# Sheet1.net
KiCad netlist of a schematic drawn in Altium Designer
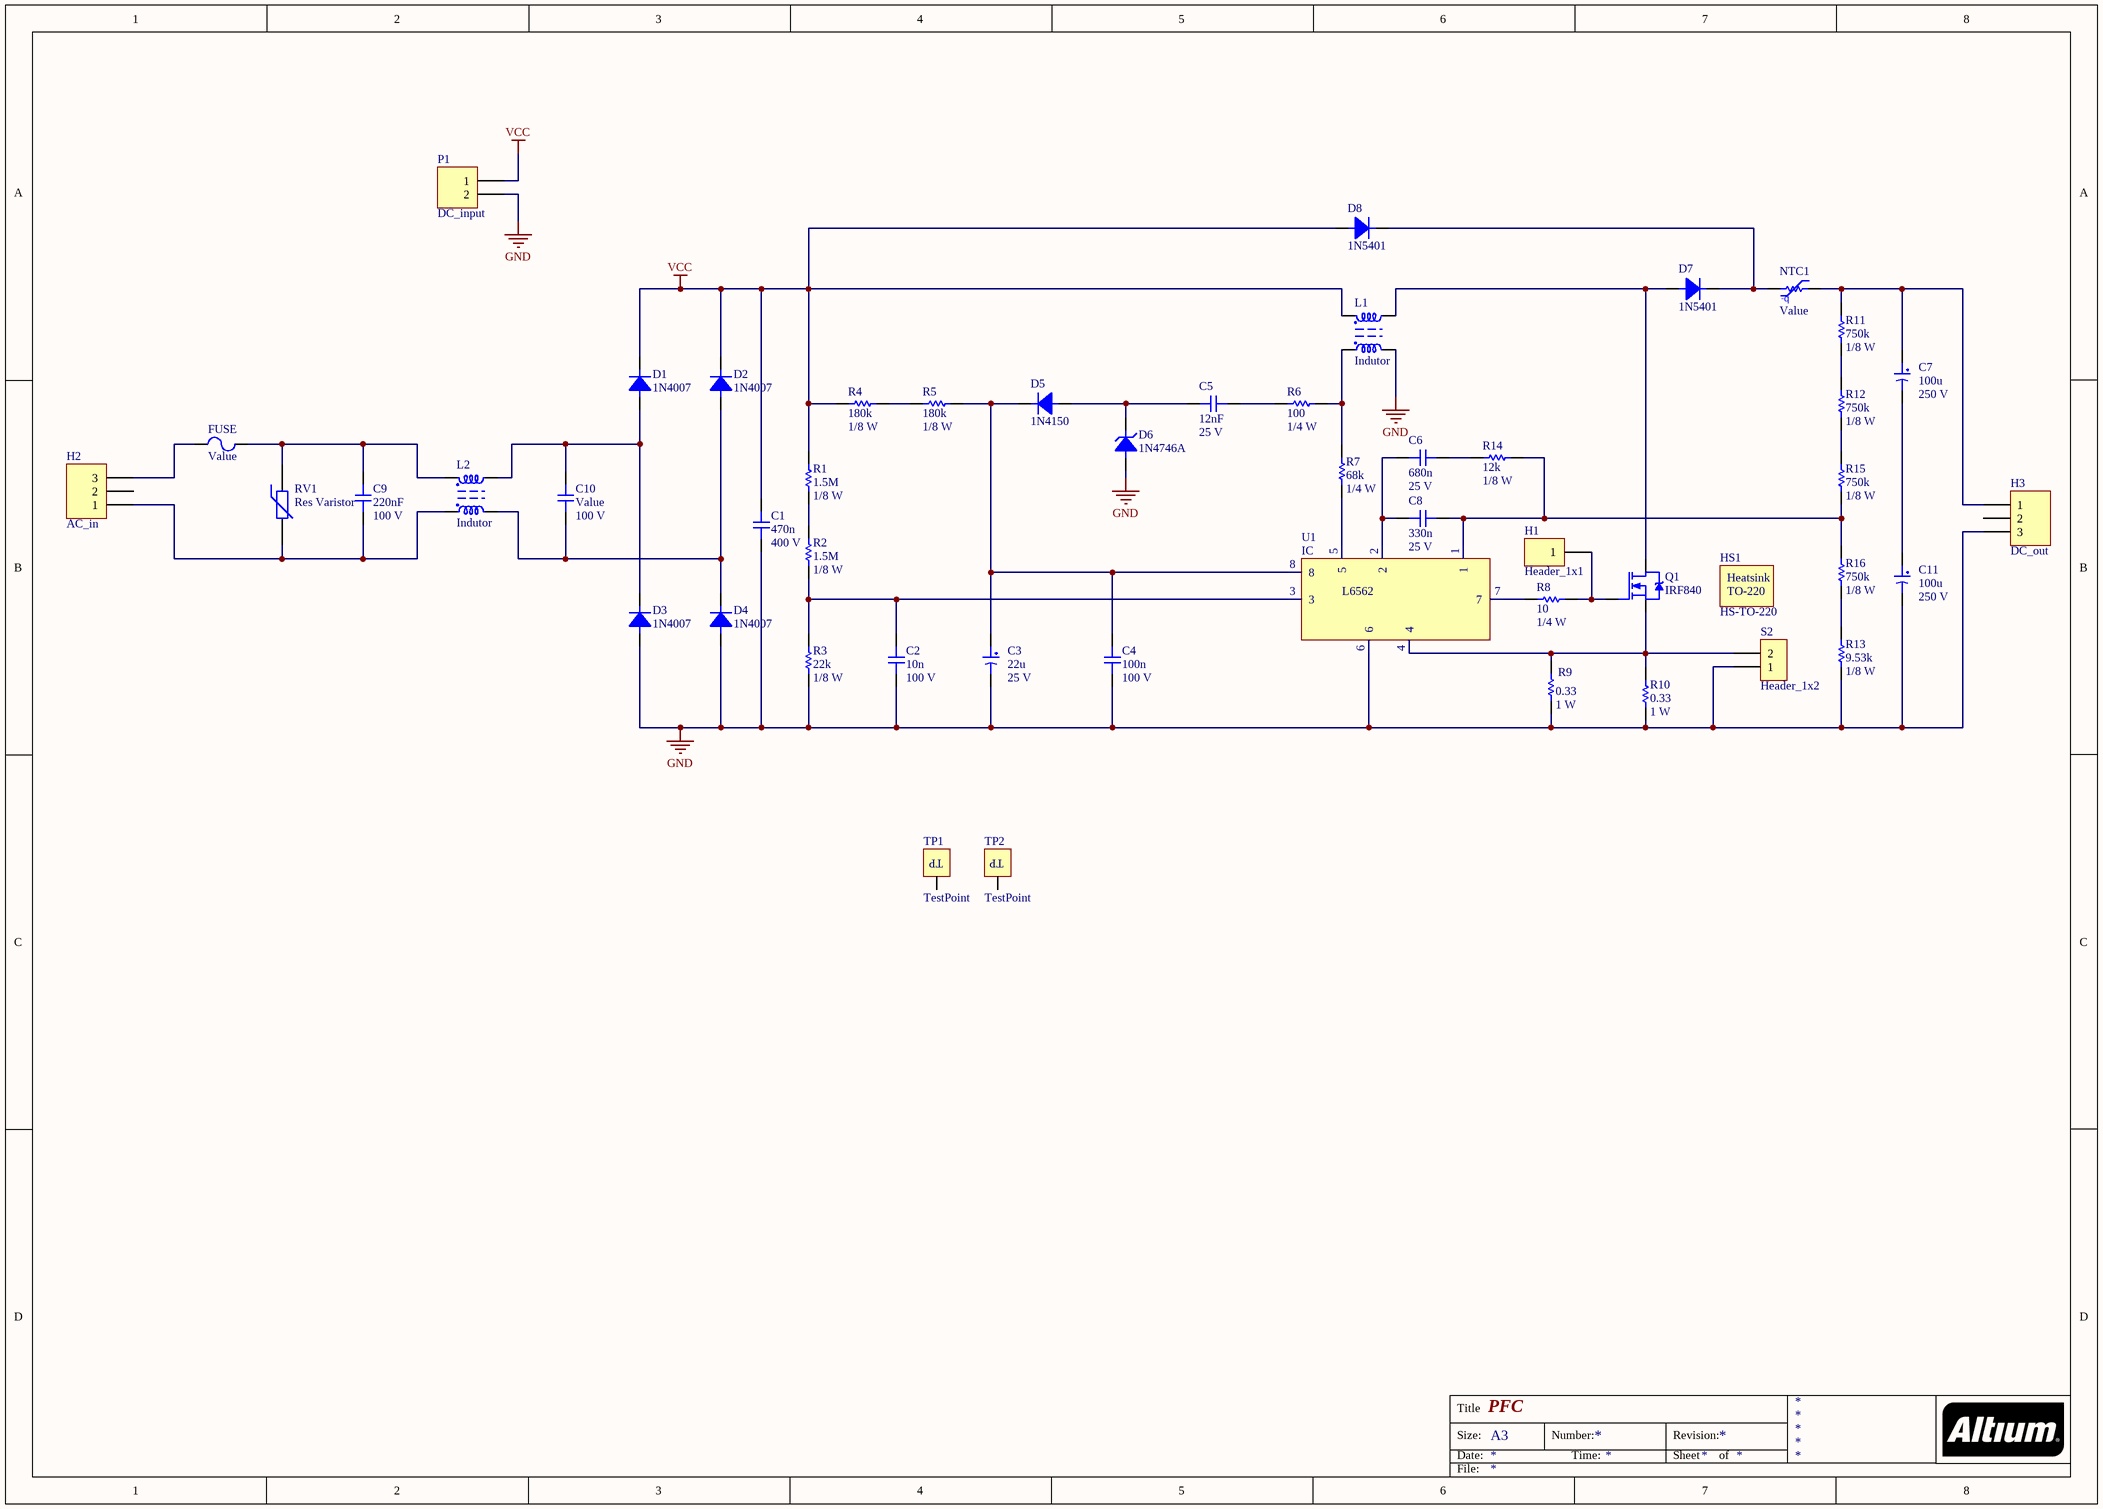
[diagram p0: Sheet1.SchDoc]

(export (version "E")
  (design (tool "Eeschema 10.0.6"))
  (components
    (comp (ref "C1")
      (value "470n")
      (footprint "AXIAL-1.0")
      (description "Capacitor")
      (fields (field (name "VOLTAGE") "400 V") (field (name "PUBLISHER") "Altium Limited"))
      (libsource (lib "GPDSE") (part "Capacitor"))
    )
    (comp (ref "C2")
      (value "10n")
      (footprint "0805C")
      (description "Capacitor")
      (fields (field (name "VOLTAGE") "100 V") (field (name "PUBLISHER") "Altium Limited"))
      (libsource (lib "GPDSE") (part "Capacitor"))
    )
    (comp (ref "C3")
      (value "22u")
      (footprint "CP-5.0mm-11.0mm-2.0mm")
      (description "Electrolytic Capacitor")
      (fields (field (name "VOLTAGE") "25 V"))
      (libsource (lib "GPDSE") (part "Capacitor-Electrolytic"))
    )
    (comp (ref "C4")
      (value "100n")
      (footprint "0805C")
      (description "Capacitor")
      (fields (field (name "VOLTAGE") "100 V") (field (name "PUBLISHER") "Altium Limited"))
      (libsource (lib "GPDSE") (part "Capacitor"))
    )
    (comp (ref "C5")
      (value "12nF")
      (footprint "C100-200-100")
      (description "Capacitor")
      (fields (field (name "VOLTAGE") "25 V") (field (name "PUBLISHER") "Altium Limited"))
      (libsource (lib "GPDSE") (part "Capacitor"))
    )
    (comp (ref "C6")
      (value "680n")
      (footprint "C200-350-150")
      (description "Capacitor")
      (fields (field (name "VOLTAGE") "25 V") (field (name "PUBLISHER") "Altium Limited"))
      (libsource (lib "GPDSE") (part "Capacitor"))
    )
    (comp (ref "C7")
      (value "100u")
      (footprint "CP-16.0mm-25.0mm-7.5mm")
      (description "Electrolytic Capacitor")
      (fields (field (name "VOLTAGE") "250 V"))
      (libsource (lib "GPDSE") (part "Capacitor-Electrolytic"))
    )
    (comp (ref "C8")
      (value "330n")
      (footprint "C200-350-150")
      (description "Capacitor")
      (fields (field (name "VOLTAGE") "25 V") (field (name "PUBLISHER") "Altium Limited"))
      (libsource (lib "GPDSE") (part "Capacitor"))
    )
    (comp (ref "C9")
      (value "220nF")
      (footprint "C590-695-330")
      (description "Capacitor")
      (fields (field (name "VOLTAGE") "100 V") (field (name "PUBLISHER") "Altium Limited"))
      (libsource (lib "GPDSE") (part "Capacitor"))
    )
    (comp (ref "C10")
      (value "Value")
      (footprint "C590-695-330")
      (description "Capacitor")
      (fields (field (name "VOLTAGE") "100 V") (field (name "PUBLISHER") "Altium Limited"))
      (libsource (lib "GPDSE") (part "Capacitor"))
    )
    (comp (ref "C11")
      (value "100u")
      (footprint "CP-16.0mm-25.0mm-7.5mm")
      (description "Electrolytic Capacitor")
      (fields (field (name "VOLTAGE") "250 V"))
      (libsource (lib "GPDSE") (part "Capacitor-Electrolytic"))
    )
    (comp (ref "D1")
      (value "1N4007")
      (footprint "DO-41-Plastic")
      (description "General Purpose Rectifier")
      (libsource (lib "GPDSE") (part "1N4007"))
    )
    (comp (ref "D2")
      (value "1N4007")
      (footprint "DO-41-Plastic")
      (description "General Purpose Rectifier")
      (libsource (lib "GPDSE") (part "1N4007"))
    )
    (comp (ref "D3")
      (value "1N4007")
      (footprint "DO-41-Plastic")
      (description "General Purpose Rectifier")
      (libsource (lib "GPDSE") (part "1N4007"))
    )
    (comp (ref "D4")
      (value "1N4007")
      (footprint "DO-41-Plastic")
      (description "General Purpose Rectifier")
      (libsource (lib "GPDSE") (part "1N4007"))
    )
    (comp (ref "D5")
      (value "1N4150")
      (footprint "DO-35-Glass")
      (description "Small Signal Diode")
      (libsource (lib "GPDSE") (part "1N914A"))
    )
    (comp (ref "D6")
      (value "1N4746A")
      (footprint "DO-41-Glass")
      (description "Zener Diode")
      (libsource (lib "GPDSE") (part "1N4746A"))
    )
    (comp (ref "D7")
      (value "1N5401")
      (footprint "DO-201-Plastic")
      (description "3 Amp Rectifier")
      (libsource (lib "GPDSE") (part "1N5401"))
    )
    (comp (ref "D8")
      (value "1N5401")
      (footprint "DO-201-Plastic")
      (description "3 Amp Rectifier")
      (libsource (lib "GPDSE") (part "1N5401"))
    )
    (comp (ref "FUSE")
      (value "Value")
      (footprint "Fuse")
      (description "Negative Temperature Coefficient Thermistor")
      (libsource (lib "AltiumDesigner") (part "FUSE"))
    )
    (comp (ref "H1")
      (value "Header_1x1")
      (footprint "HDR1X1")
      (description "Header 1 Line 1 Pin")
      (fields (field (name "PUBLISHER") "Altium Limited"))
      (libsource (lib "R2R") (part "Header_1x1"))
    )
    (comp (ref "H2")
      (value "AC_in")
      (footprint "TB03")
      (description "Bloco terminal 1x3")
      (libsource (lib "") (part "Terminal_1x3_1"))
    )
    (comp (ref "H3")
      (value "DC_out")
      (footprint "TB03")
      (description "Bloco terminal 1x3")
      (libsource (lib "R2R") (part "Terminal_1x3"))
    )
    (comp (ref "HS1")
      (value "HS-TO-220")
      (footprint "HS-TO-220-183012")
      (description "Heatsink TO-220")
      (libsource (lib "GPDSE") (part "HS-TO-220"))
    )
    (comp (ref "L1")
      (value "Indutor")
      (footprint "TRZ30.010.1")
      (description "Indutor Acoplado - Filtro EMI")
      (libsource (lib "AltiumDesigner") (part "Indutor"))
    )
    (comp (ref "L2")
      (value "Indutor")
      (footprint "IndutorAcoplado")
      (description "Indutor Acoplado - Filtro EMI")
      (libsource (lib "AltiumDesigner") (part "Indutor"))
    )
    (comp (ref "NTC1")
      (value "Value")
      (footprint "Thermistor-315mil")
      (description "Negative Temperature Coefficient Thermistor")
      (libsource (lib "AltiumDesigner") (part "NTC"))
    )
    (comp (ref "P1")
      (value "DC_input")
      (footprint "KRE_2")
      (description "Terminal Block 1x2")
      (libsource (lib "GPDSE") (part "KRE_2"))
    )
    (comp (ref "Q1")
      (value "IRF840")
      (footprint "TO-220/123")
      (description "HEXFET Power MOSFET")
      (libsource (lib "GPDSE") (part "IRFZ46N"))
    )
    (comp (ref "R1")
      (value "1.5M")
      (footprint "0805R")
      (description "Resistor")
      (fields
        (field (name "TOLERANCE") "5%")
        (field (name "POWER") "1/8 W")
        (field (name "PUBLISHER") "Altium Limited")
      )
      (libsource (lib "GPDSE") (part "Resistor"))
    )
    (comp (ref "R2")
      (value "1.5M")
      (footprint "0805R")
      (description "Resistor")
      (fields
        (field (name "TOLERANCE") "5%")
        (field (name "POWER") "1/8 W")
        (field (name "PUBLISHER") "Altium Limited")
      )
      (libsource (lib "GPDSE") (part "Resistor"))
    )
    (comp (ref "R3")
      (value "22k")
      (footprint "0805R")
      (description "Resistor")
      (fields
        (field (name "TOLERANCE") "5%")
        (field (name "POWER") "1/8 W")
        (field (name "PUBLISHER") "Altium Limited")
      )
      (libsource (lib "GPDSE") (part "Resistor"))
    )
    (comp (ref "R4")
      (value "180k")
      (footprint "0805R")
      (description "Resistor")
      (fields
        (field (name "TOLERANCE") "5%")
        (field (name "POWER") "1/8 W")
        (field (name "PUBLISHER") "Altium Limited")
      )
      (libsource (lib "GPDSE") (part "Resistor"))
    )
    (comp (ref "R5")
      (value "180k")
      (footprint "0805R")
      (description "Resistor")
      (fields
        (field (name "TOLERANCE") "5%")
        (field (name "POWER") "1/8 W")
        (field (name "PUBLISHER") "Altium Limited")
      )
      (libsource (lib "GPDSE") (part "Resistor"))
    )
    (comp (ref "R6")
      (value "100")
      (footprint "R400-2.0mm")
      (description "Resistor")
      (fields
        (field (name "TOLERANCE") "5%")
        (field (name "POWER") "1/4 W")
        (field (name "PUBLISHER") "Altium Limited")
      )
      (libsource (lib "GPDSE") (part "Resistor"))
    )
    (comp (ref "R7")
      (value "68k")
      (footprint "R400-2.0mm")
      (description "Resistor")
      (fields
        (field (name "TOLERANCE") "5%")
        (field (name "POWER") "1/4 W")
        (field (name "PUBLISHER") "Altium Limited")
      )
      (libsource (lib "GPDSE") (part "Resistor"))
    )
    (comp (ref "R8")
      (value "10")
      (footprint "R400-2.0mm")
      (description "Resistor")
      (fields
        (field (name "TOLERANCE") "5%")
        (field (name "POWER") "1/4 W")
        (field (name "PUBLISHER") "Altium Limited")
      )
      (libsource (lib "GPDSE") (part "Resistor"))
    )
    (comp (ref "R9")
      (value "0.33")
      (footprint "R-AC01")
      (description "Power Resistor")
      (fields
        (field (name "TOLERANCE") "5%")
        (field (name "POWER") "1 W")
        (field (name "PUBLISHER") "Altium Limited")
      )
      (libsource (lib "GPDSE") (part "ResistorPower"))
    )
    (comp (ref "R10")
      (value "0.33")
      (footprint "R-AC01")
      (description "Power Resistor")
      (fields
        (field (name "TOLERANCE") "5%")
        (field (name "POWER") "1 W")
        (field (name "PUBLISHER") "Altium Limited")
      )
      (libsource (lib "GPDSE") (part "ResistorPower"))
    )
    (comp (ref "R11")
      (value "750k")
      (footprint "0805R")
      (description "Resistor")
      (fields
        (field (name "TOLERANCE") "5%")
        (field (name "POWER") "1/8 W")
        (field (name "PUBLISHER") "Altium Limited")
      )
      (libsource (lib "GPDSE") (part "Resistor"))
    )
    (comp (ref "R12")
      (value "750k")
      (footprint "0805R")
      (description "Resistor")
      (fields
        (field (name "TOLERANCE") "5%")
        (field (name "POWER") "1/8 W")
        (field (name "PUBLISHER") "Altium Limited")
      )
      (libsource (lib "GPDSE") (part "Resistor"))
    )
    (comp (ref "R13")
      (value "9.53k")
      (footprint "0805R")
      (description "Resistor")
      (fields
        (field (name "TOLERANCE") "5%")
        (field (name "POWER") "1/8 W")
        (field (name "PUBLISHER") "Altium Limited")
      )
      (libsource (lib "GPDSE") (part "Resistor"))
    )
    (comp (ref "R14")
      (value "12k")
      (footprint "0805R")
      (description "Resistor")
      (fields
        (field (name "TOLERANCE") "5%")
        (field (name "POWER") "1/8 W")
        (field (name "PUBLISHER") "Altium Limited")
      )
      (libsource (lib "GPDSE") (part "Resistor"))
    )
    (comp (ref "R15")
      (value "750k")
      (footprint "0805R")
      (description "Resistor")
      (fields
        (field (name "TOLERANCE") "5%")
        (field (name "POWER") "1/8 W")
        (field (name "PUBLISHER") "Altium Limited")
      )
      (libsource (lib "GPDSE") (part "Resistor"))
    )
    (comp (ref "R16")
      (value "750k")
      (footprint "0805R")
      (description "Resistor")
      (fields
        (field (name "TOLERANCE") "5%")
        (field (name "POWER") "1/8 W")
        (field (name "PUBLISHER") "Altium Limited")
      )
      (libsource (lib "GPDSE") (part "Resistor"))
    )
    (comp (ref "RV1")
      (value "Res Varistor")
      (footprint "C400-550-150")
      (description "Varistor (Voltage-Sensitive Resistor)")
      (fields (field (name "PUBLISHER") "Altium Limited"))
      (libsource (lib "Miscellaneous Devices") (part "Res Varistor"))
    )
    (comp (ref "S2")
      (value "Header_1x2")
      (footprint "HDR-M-1x2-2.54mm-180-9.2mm")
      (description "Header, 1 Line, 2 Columns, 2 Pins")
      (fields (field (name "PUBLISHER") "Altium Limited"))
      (libsource (lib "GPDSE") (part "Header_1x2"))
    )
    (comp (ref "TP1")
      (value "TestPoint")
      (footprint "FD")
      (description "Test Point")
      (libsource (lib "GPDSE") (part "TestPoint"))
    )
    (comp (ref "TP2")
      (value "TestPoint")
      (footprint "FD")
      (description "Test Point")
      (libsource (lib "GPDSE") (part "TestPoint"))
    )
    (comp (ref "U1")
      (value "IC")
      (footprint "SO8_L")
      (description "PFC Controller")
      (libsource (lib "L6562") (part "L6562"))
    )
  )
  (nets
    (net (code "1") (name "GND") (class "Default")
      (node (ref "C1") (pin "2") (pinfunction "2_2") (pintype "passive"))
      (node (ref "C11") (pin "2") (pinfunction "2_2") (pintype "passive"))
      (node (ref "C2") (pin "2") (pinfunction "2_2") (pintype "passive"))
      (node (ref "C3") (pin "2") (pinfunction "2_2") (pintype "passive"))
      (node (ref "C4") (pin "2") (pinfunction "2_2") (pintype "passive"))
      (node (ref "D3") (pin "A") (pinfunction "A_A") (pintype "passive"))
      (node (ref "D4") (pin "A") (pinfunction "A_A") (pintype "passive"))
      (node (ref "D6") (pin "A") (pinfunction "A_A") (pintype "passive"))
      (node (ref "H3") (pin "3") (pinfunction "3_3") (pintype "passive"))
      (node (ref "L1") (pin "4") (pinfunction "4_4") (pintype "passive"))
      (node (ref "P1") (pin "2") (pinfunction "2_2") (pintype "passive"))
      (node (ref "R10") (pin "2") (pinfunction "2_2") (pintype "passive"))
      (node (ref "R13") (pin "1") (pinfunction "1_1") (pintype "passive"))
      (node (ref "R3") (pin "1") (pinfunction "1_1") (pintype "passive"))
      (node (ref "R9") (pin "2") (pinfunction "2_2") (pintype "passive"))
      (node (ref "S2") (pin "1") (pinfunction "1_1") (pintype "passive"))
      (node (ref "U1") (pin "6") (pinfunction "6_6") (pintype "passive"))
    )
    (net (code "2") (name "Net-(C2-Pad1)") (class "Default")
      (node (ref "C2") (pin "1") (pinfunction "1_1") (pintype "passive"))
      (node (ref "R2") (pin "2") (pinfunction "2_2") (pintype "passive"))
      (node (ref "R3") (pin "2") (pinfunction "2_2") (pintype "passive"))
      (node (ref "U1") (pin "3") (pinfunction "3_3") (pintype "passive"))
    )
    (net (code "3") (name "Net-(C3-Pad1)") (class "Default")
      (node (ref "C3") (pin "1") (pinfunction "1_1") (pintype "passive"))
      (node (ref "C4") (pin "1") (pinfunction "1_1") (pintype "passive"))
      (node (ref "D5") (pin "K") (pinfunction "K_K") (pintype "passive"))
      (node (ref "R5") (pin "2") (pinfunction "2_2") (pintype "passive"))
      (node (ref "U1") (pin "8") (pinfunction "8_8") (pintype "passive"))
    )
    (net (code "4") (name "Net-(C5-Pad1)") (class "Default")
      (node (ref "C5") (pin "1") (pinfunction "1_1") (pintype "passive"))
      (node (ref "D5") (pin "A") (pinfunction "A_A") (pintype "passive"))
      (node (ref "D6") (pin "K") (pinfunction "K_K") (pintype "passive"))
    )
    (net (code "5") (name "Net-(C5-Pad2)") (class "Default")
      (node (ref "C5") (pin "2") (pinfunction "2_2") (pintype "passive"))
      (node (ref "R6") (pin "1") (pinfunction "1_1") (pintype "passive"))
    )
    (net (code "6") (name "Net-(C6-Pad1)") (class "Default")
      (node (ref "C6") (pin "1") (pinfunction "1_1") (pintype "passive"))
      (node (ref "C8") (pin "1") (pinfunction "1_1") (pintype "passive"))
      (node (ref "U1") (pin "2") (pinfunction "2_2") (pintype "passive"))
    )
    (net (code "7") (name "Net-(C6-Pad2)") (class "Default")
      (node (ref "C6") (pin "2") (pinfunction "2_2") (pintype "passive"))
      (node (ref "R14") (pin "2") (pinfunction "2_2") (pintype "passive"))
    )
    (net (code "8") (name "Net-(C7-Pad1)") (class "Default")
      (node (ref "C7") (pin "1") (pinfunction "1_1") (pintype "passive"))
      (node (ref "H3") (pin "1") (pinfunction "1_1") (pintype "passive"))
      (node (ref "NTC1") (pin "2") (pinfunction "2_2") (pintype "passive"))
      (node (ref "R11") (pin "2") (pinfunction "2_2") (pintype "passive"))
    )
    (net (code "9") (name "Net-(C8-Pad2)") (class "Default")
      (node (ref "C8") (pin "2") (pinfunction "2_2") (pintype "passive"))
      (node (ref "R14") (pin "1") (pinfunction "1_1") (pintype "passive"))
      (node (ref "R15") (pin "1") (pinfunction "1_1") (pintype "passive"))
      (node (ref "R16") (pin "2") (pinfunction "2_2") (pintype "passive"))
      (node (ref "U1") (pin "1") (pinfunction "1_1") (pintype "passive"))
    )
    (net (code "10") (name "Net-(C9-Pad1)") (class "Default")
      (node (ref "C9") (pin "1") (pinfunction "1_1") (pintype "passive"))
      (node (ref "FUSE") (pin "2") (pinfunction "2_2") (pintype "passive"))
      (node (ref "L2") (pin "1") (pinfunction "1_1") (pintype "passive"))
      (node (ref "RV1") (pin "1") (pinfunction "1_1") (pintype "passive"))
    )
    (net (code "11") (name "Net-(C9-Pad2)") (class "Default")
      (node (ref "C9") (pin "2") (pinfunction "2_2") (pintype "passive"))
      (node (ref "H2") (pin "1") (pinfunction "1_1") (pintype "passive"))
      (node (ref "L2") (pin "3") (pinfunction "3_3") (pintype "passive"))
      (node (ref "RV1") (pin "2") (pinfunction "2_2") (pintype "passive"))
    )
    (net (code "12") (name "Net-(C10-Pad1)") (class "Default")
      (node (ref "C10") (pin "1") (pinfunction "1_1") (pintype "passive"))
      (node (ref "D2") (pin "A") (pinfunction "A_A") (pintype "passive"))
      (node (ref "D4") (pin "K") (pinfunction "K_K") (pintype "passive"))
      (node (ref "L2") (pin "4") (pinfunction "4_4") (pintype "passive"))
    )
    (net (code "13") (name "Net-(C10-Pad2)") (class "Default")
      (node (ref "C10") (pin "2") (pinfunction "2_2") (pintype "passive"))
      (node (ref "D1") (pin "A") (pinfunction "A_A") (pintype "passive"))
      (node (ref "D3") (pin "K") (pinfunction "K_K") (pintype "passive"))
      (node (ref "L2") (pin "2") (pinfunction "2_2") (pintype "passive"))
    )
    (net (code "14") (name "Net-(C11-Pad1)") (class "Default")
      (node (ref "C11") (pin "1") (pinfunction "1_1") (pintype "passive"))
      (node (ref "C7") (pin "2") (pinfunction "2_2") (pintype "passive"))
    )
    (net (code "15") (name "Net-(D7-PadA)") (class "Default")
      (node (ref "D7") (pin "A") (pinfunction "A_A") (pintype "passive"))
      (node (ref "L1") (pin "2") (pinfunction "2_2") (pintype "passive"))
      (node (ref "Q1") (pin "D") (pinfunction "D_D") (pintype "passive"))
    )
    (net (code "16") (name "Net-(D7-PadK)") (class "Default")
      (node (ref "D7") (pin "K") (pinfunction "K_K") (pintype "passive"))
      (node (ref "D8") (pin "K") (pinfunction "K_K") (pintype "passive"))
      (node (ref "NTC1") (pin "1") (pinfunction "1_1") (pintype "passive"))
    )
    (net (code "17") (name "Net-(FUSE-Pad1)") (class "Default")
      (node (ref "FUSE") (pin "1") (pinfunction "1_1") (pintype "passive"))
      (node (ref "H2") (pin "3") (pinfunction "3_3") (pintype "passive"))
    )
    (net (code "18") (name "Net-(H1-Pad1)") (class "Default")
      (node (ref "H1") (pin "1") (pinfunction "1_1") (pintype "passive"))
      (node (ref "Q1") (pin "G") (pinfunction "G_G") (pintype "passive"))
      (node (ref "R8") (pin "2") (pinfunction "2_2") (pintype "passive"))
    )
    (net (code "19") (name "Net-(L1-Pad3)") (class "Default")
      (node (ref "L1") (pin "3") (pinfunction "3_3") (pintype "passive"))
      (node (ref "R6") (pin "2") (pinfunction "2_2") (pintype "passive"))
      (node (ref "R7") (pin "2") (pinfunction "2_2") (pintype "passive"))
    )
    (net (code "20") (name "Net-(Q1-PadS)") (class "Default")
      (node (ref "Q1") (pin "S") (pinfunction "S_S") (pintype "passive"))
      (node (ref "R10") (pin "1") (pinfunction "1_1") (pintype "passive"))
      (node (ref "R9") (pin "1") (pinfunction "1_1") (pintype "passive"))
      (node (ref "S2") (pin "2") (pinfunction "2_2") (pintype "passive"))
      (node (ref "U1") (pin "4") (pinfunction "4_4") (pintype "passive"))
    )
    (net (code "21") (name "Net-(R1-Pad2)") (class "Default")
      (node (ref "R1") (pin "2") (pinfunction "2_2") (pintype "passive"))
      (node (ref "R2") (pin "1") (pinfunction "1_1") (pintype "passive"))
    )
    (net (code "22") (name "Net-(R4-Pad2)") (class "Default")
      (node (ref "R4") (pin "2") (pinfunction "2_2") (pintype "passive"))
      (node (ref "R5") (pin "1") (pinfunction "1_1") (pintype "passive"))
    )
    (net (code "23") (name "Net-(R7-Pad1)") (class "Default")
      (node (ref "R7") (pin "1") (pinfunction "1_1") (pintype "passive"))
      (node (ref "U1") (pin "5") (pinfunction "5_5") (pintype "passive"))
    )
    (net (code "24") (name "Net-(R8-Pad1)") (class "Default")
      (node (ref "R8") (pin "1") (pinfunction "1_1") (pintype "passive"))
      (node (ref "U1") (pin "7") (pinfunction "7_7") (pintype "passive"))
    )
    (net (code "25") (name "Net-(R11-Pad1)") (class "Default")
      (node (ref "R11") (pin "1") (pinfunction "1_1") (pintype "passive"))
      (node (ref "R12") (pin "2") (pinfunction "2_2") (pintype "passive"))
    )
    (net (code "26") (name "Net-(R12-Pad1)") (class "Default")
      (node (ref "R12") (pin "1") (pinfunction "1_1") (pintype "passive"))
      (node (ref "R15") (pin "2") (pinfunction "2_2") (pintype "passive"))
    )
    (net (code "27") (name "Net-(R13-Pad2)") (class "Default")
      (node (ref "R13") (pin "2") (pinfunction "2_2") (pintype "passive"))
      (node (ref "R16") (pin "1") (pinfunction "1_1") (pintype "passive"))
    )
    (net (code "28") (name "VCC") (class "Default")
      (node (ref "C1") (pin "1") (pinfunction "1_1") (pintype "passive"))
      (node (ref "D1") (pin "K") (pinfunction "K_K") (pintype "passive"))
      (node (ref "D2") (pin "K") (pinfunction "K_K") (pintype "passive"))
      (node (ref "D8") (pin "A") (pinfunction "A_A") (pintype "passive"))
      (node (ref "L1") (pin "1") (pinfunction "1_1") (pintype "passive"))
      (node (ref "P1") (pin "1") (pinfunction "1_1") (pintype "passive"))
      (node (ref "R1") (pin "1") (pinfunction "1_1") (pintype "passive"))
      (node (ref "R4") (pin "1") (pinfunction "1_1") (pintype "passive"))
    )
    (net (code "29") (name "unconnected-(H2-Pad2)") (class "Default")
      (node (ref "H2") (pin "2") (pinfunction "2_2") (pintype "passive"))
    )
    (net (code "30") (name "unconnected-(H3-Pad2)") (class "Default")
      (node (ref "H3") (pin "2") (pinfunction "2_2") (pintype "passive"))
    )
    (net (code "31") (name "unconnected-(TP1-TP-Pad1)") (class "Default")
      (node (ref "TP1") (pin "1") (pinfunction "TP_1") (pintype "passive"))
    )
    (net (code "32") (name "unconnected-(TP2-TP-Pad1)") (class "Default")
      (node (ref "TP2") (pin "1") (pinfunction "TP_1") (pintype "passive"))
    )
  )
)
